# Power_Supply.net
KiCad netlist of a schematic drawn in EAGLE
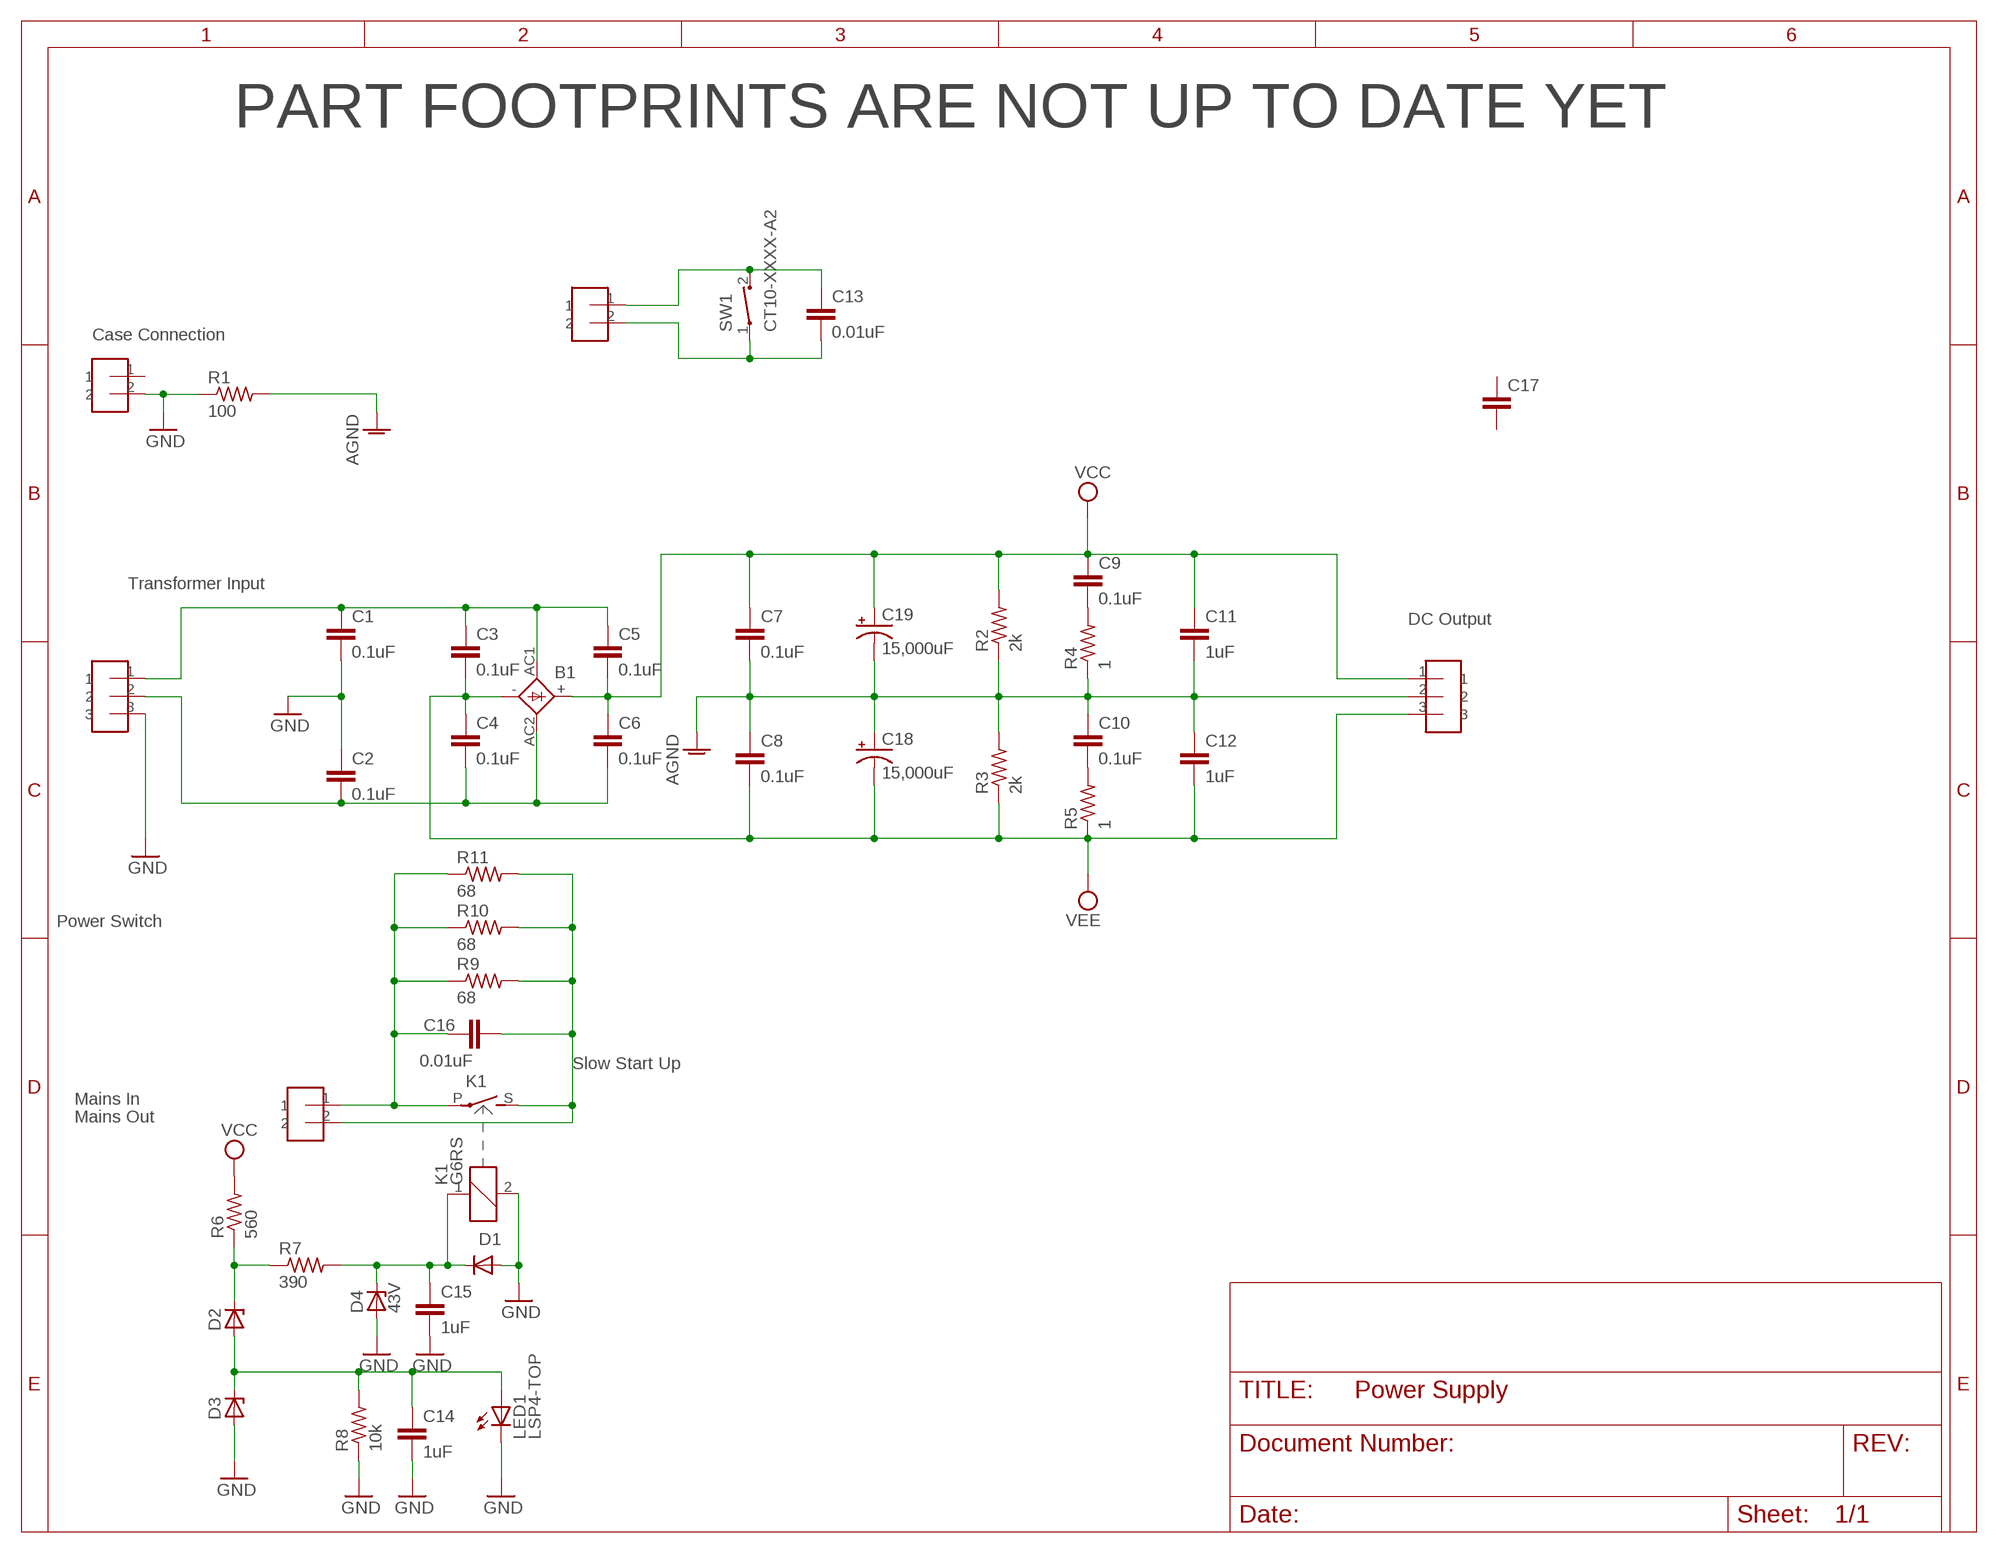
[diagram p0: schematic, sheet 1]

(export (version "E")
  (design (tool "Eeschema 10.0.6"))
  (components
    (comp (ref "B1")
      (value "GBPC1")
      (footprint "eagle-import:GBPC1")
      (libsource (lib "eagle-import") (part "GBPC1"))
    )
    (comp (ref "C1")
      (value "0.1uF")
      (footprint "eagle-import:C025-060X050")
      (libsource (lib "eagle-import") (part "C-EU025-060X050"))
    )
    (comp (ref "C2")
      (value "0.1uF")
      (footprint "eagle-import:C025-060X050")
      (libsource (lib "eagle-import") (part "C-EU025-060X050"))
    )
    (comp (ref "C3")
      (value "0.1uF")
      (footprint "eagle-import:C025-060X050")
      (libsource (lib "eagle-import") (part "C-EU025-060X050"))
    )
    (comp (ref "C4")
      (value "0.1uF")
      (footprint "eagle-import:C025-060X050")
      (libsource (lib "eagle-import") (part "C-EU025-060X050"))
    )
    (comp (ref "C5")
      (value "0.1uF")
      (footprint "eagle-import:C025-060X050")
      (libsource (lib "eagle-import") (part "C-EU025-060X050"))
    )
    (comp (ref "C6")
      (value "0.1uF")
      (footprint "eagle-import:C025-060X050")
      (libsource (lib "eagle-import") (part "C-EU025-060X050"))
    )
    (comp (ref "C7")
      (value "0.1uF")
      (footprint "eagle-import:C025-060X050")
      (libsource (lib "eagle-import") (part "C-EU025-060X050"))
    )
    (comp (ref "C8")
      (value "0.1uF")
      (footprint "eagle-import:C025-060X050")
      (libsource (lib "eagle-import") (part "C-EU025-060X050"))
    )
    (comp (ref "C9")
      (value "0.1uF")
      (footprint "eagle-import:C025-060X050")
      (libsource (lib "eagle-import") (part "C-EU025-060X050"))
    )
    (comp (ref "C10")
      (value "0.1uF")
      (footprint "eagle-import:C025-060X050")
      (libsource (lib "eagle-import") (part "C-EU025-060X050"))
    )
    (comp (ref "C11")
      (value "1uF")
      (footprint "eagle-import:C025-060X050")
      (libsource (lib "eagle-import") (part "C-EU025-060X050"))
    )
    (comp (ref "C12")
      (value "1uF")
      (footprint "eagle-import:C025-060X050")
      (libsource (lib "eagle-import") (part "C-EU025-060X050"))
    )
    (comp (ref "C13")
      (value "0.01uF")
      (footprint "eagle-import:C025-060X050")
      (libsource (lib "eagle-import") (part "C-EU025-060X050"))
    )
    (comp (ref "C14")
      (value "1uF")
      (footprint "eagle-import:C025-060X050")
      (libsource (lib "eagle-import") (part "C-EU025-060X050"))
    )
    (comp (ref "C15")
      (value "1uF")
      (footprint "eagle-import:C025-060X050")
      (libsource (lib "eagle-import") (part "C-EU025-060X050"))
    )
    (comp (ref "C16")
      (value "0.01uF")
      (footprint "eagle-import:C025-060X050")
      (libsource (lib "eagle-import") (part "C-EU025-060X050"))
    )
    (comp (ref "C17")
      (value "C-EU025-060X050")
      (footprint "eagle-import:C025-060X050")
      (libsource (lib "eagle-import") (part "C-EU025-060X050"))
    )
    (comp (ref "C18")
      (value "15,000uF")
      (footprint "eagle-import:E7,5-16")
      (libsource (lib "eagle-import") (part "CPOL-USE7.5-16"))
    )
    (comp (ref "C19")
      (value "15,000uF")
      (footprint "eagle-import:E7,5-16")
      (libsource (lib "eagle-import") (part "CPOL-USE7.5-16"))
    )
    (comp (ref "D1")
      (value "1N4004")
      (footprint "eagle-import:DO41-10")
      (libsource (lib "eagle-import") (part "1N4004"))
    )
    (comp (ref "D2")
      (value "ZENER-DIODEDO34-7")
      (footprint "eagle-import:DO34Z7")
      (libsource (lib "eagle-import") (part "ZENER-DIODEDO34-7"))
    )
    (comp (ref "D3")
      (value "ZENER-DIODEDO34-7")
      (footprint "eagle-import:DO34Z7")
      (libsource (lib "eagle-import") (part "ZENER-DIODEDO34-7"))
    )
    (comp (ref "D4")
      (value "43V")
      (footprint "eagle-import:DO34Z7")
      (libsource (lib "eagle-import") (part "ZENER-DIODEDO34-7"))
    )
    (comp (ref "K1")
      (value "G6RS")
      (footprint "eagle-import:G6RS")
      (libsource (lib "eagle-import") (part "G6RS"))
    )
    (comp (ref "LED1")
      (value "LSP4-TOP")
      (footprint "eagle-import:P47F-TOP")
      (libsource (lib "eagle-import") (part "P4-TOPLS"))
    )
    (comp (ref "R1")
      (value "100")
      (footprint "eagle-import:0617_22")
      (libsource (lib "eagle-import") (part "R-US_0617/22"))
    )
    (comp (ref "R2")
      (value "2k")
      (footprint "eagle-import:0617_22")
      (libsource (lib "eagle-import") (part "R-US_0617/22"))
    )
    (comp (ref "R3")
      (value "2k")
      (footprint "eagle-import:0617_22")
      (libsource (lib "eagle-import") (part "R-US_0617/22"))
    )
    (comp (ref "R4")
      (value "1")
      (footprint "eagle-import:0617_22")
      (libsource (lib "eagle-import") (part "R-US_0617/22"))
    )
    (comp (ref "R5")
      (value "1")
      (footprint "eagle-import:0617_22")
      (libsource (lib "eagle-import") (part "R-US_0617/22"))
    )
    (comp (ref "R6")
      (value "560")
      (footprint "eagle-import:0617_22")
      (libsource (lib "eagle-import") (part "R-US_0617/22"))
    )
    (comp (ref "R7")
      (value "390")
      (footprint "eagle-import:0617_22")
      (libsource (lib "eagle-import") (part "R-US_0617/22"))
    )
    (comp (ref "R8")
      (value "10k")
      (footprint "eagle-import:0617_22")
      (libsource (lib "eagle-import") (part "R-US_0617/22"))
    )
    (comp (ref "R9")
      (value "68")
      (footprint "eagle-import:0617_22")
      (libsource (lib "eagle-import") (part "R-US_0617/22"))
    )
    (comp (ref "R10")
      (value "68")
      (footprint "eagle-import:0617_22")
      (libsource (lib "eagle-import") (part "R-US_0617/22"))
    )
    (comp (ref "R11")
      (value "68")
      (footprint "eagle-import:0617_22")
      (libsource (lib "eagle-import") (part "R-US_0617/22"))
    )
    (comp (ref "SW1")
      (value "CT10-XXXX-A2")
      (footprint "eagle-import:CT10-XXXX-A2")
      (libsource (lib "eagle-import") (part "CT10-XXXX-A2"))
    )
    (comp (ref "U$1")
      (value "1X3HEADER_100MIL")
      (footprint "eagle-import:1X3_100MIL")
      (libsource (lib "eagle-import") (part "1X3HEADER_100MIL"))
    )
    (comp (ref "U$2")
      (value "1X3HEADER_100MIL")
      (footprint "eagle-import:1X3_100MIL")
      (libsource (lib "eagle-import") (part "1X3HEADER_100MIL"))
    )
    (comp (ref "U$3")
      (value "1X2HEADER_100MIL")
      (footprint "eagle-import:1X2_100MIL")
      (libsource (lib "eagle-import") (part "1X2HEADER_100MIL"))
    )
    (comp (ref "U$4")
      (value "1X2HEADER_100MIL")
      (footprint "eagle-import:1X2_100MIL")
      (libsource (lib "eagle-import") (part "1X2HEADER_100MIL"))
    )
    (comp (ref "U$5")
      (value "1X2HEADER_100MIL")
      (footprint "eagle-import:1X2_100MIL")
      (libsource (lib "eagle-import") (part "1X2HEADER_100MIL"))
    )
  )
  (nets
    (net (code "1") (name "AGND") (class "Default")
      (node (ref "C10") (pin "1") (pinfunction "1_1") (pintype "passive"))
      (node (ref "C11") (pin "2") (pinfunction "2_2") (pintype "passive"))
      (node (ref "C12") (pin "1") (pinfunction "1_1") (pintype "passive"))
      (node (ref "C18") (pin "+") (pinfunction "+_+") (pintype "passive"))
      (node (ref "C19") (pin "-") (pinfunction "-_-") (pintype "passive"))
      (node (ref "C7") (pin "2") (pinfunction "2_2") (pintype "passive"))
      (node (ref "C8") (pin "1") (pinfunction "1_1") (pintype "passive"))
      (node (ref "R1") (pin "2") (pinfunction "2_2") (pintype "passive"))
      (node (ref "R2") (pin "1") (pinfunction "1_1") (pintype "passive"))
      (node (ref "R3") (pin "2") (pinfunction "2_2") (pintype "passive"))
      (node (ref "R4") (pin "1") (pinfunction "1_1") (pintype "passive"))
      (node (ref "U$2") (pin "2") (pinfunction "2_2") (pintype "bidirectional"))
    )
    (net (code "2") (name "GND") (class "Default")
      (node (ref "C1") (pin "2") (pinfunction "2_2") (pintype "passive"))
      (node (ref "C14") (pin "2") (pinfunction "2_2") (pintype "passive"))
      (node (ref "C15") (pin "2") (pinfunction "2_2") (pintype "passive"))
      (node (ref "C2") (pin "1") (pinfunction "1_1") (pintype "passive"))
      (node (ref "D1") (pin "A") (pinfunction "A_A") (pintype "passive"))
      (node (ref "D3") (pin "A") (pinfunction "A_A") (pintype "passive"))
      (node (ref "D4") (pin "A") (pinfunction "A_A") (pintype "passive"))
      (node (ref "K1") (pin "2") (pinfunction "2_2") (pintype "passive"))
      (node (ref "LED1") (pin "C") (pinfunction "C_C") (pintype "passive"))
      (node (ref "R1") (pin "1") (pinfunction "1_1") (pintype "passive"))
      (node (ref "R8") (pin "1") (pinfunction "1_1") (pintype "passive"))
      (node (ref "U$1") (pin "3") (pinfunction "3_3") (pintype "bidirectional"))
      (node (ref "U$3") (pin "2") (pinfunction "2_2") (pintype "bidirectional"))
    )
    (net (code "3") (name "Net-(B1-PadAC1)") (class "Default")
      (node (ref "B1") (pin "AC1") (pinfunction "AC1_AC1") (pintype "passive"))
      (node (ref "C1") (pin "1") (pinfunction "1_1") (pintype "passive"))
      (node (ref "C3") (pin "1") (pinfunction "1_1") (pintype "passive"))
      (node (ref "C5") (pin "1") (pinfunction "1_1") (pintype "passive"))
      (node (ref "U$1") (pin "1") (pinfunction "1_1") (pintype "bidirectional"))
    )
    (net (code "4") (name "Net-(B1-PadAC2)") (class "Default")
      (node (ref "B1") (pin "AC2") (pinfunction "AC2_AC2") (pintype "passive"))
      (node (ref "C2") (pin "2") (pinfunction "2_2") (pintype "passive"))
      (node (ref "C4") (pin "2") (pinfunction "2_2") (pintype "passive"))
      (node (ref "C6") (pin "2") (pinfunction "2_2") (pintype "passive"))
      (node (ref "U$1") (pin "2") (pinfunction "2_2") (pintype "bidirectional"))
    )
    (net (code "5") (name "Net-(C9-Pad2)") (class "Default")
      (node (ref "C9") (pin "2") (pinfunction "2_2") (pintype "passive"))
      (node (ref "R4") (pin "2") (pinfunction "2_2") (pintype "passive"))
    )
    (net (code "6") (name "Net-(C10-Pad2)") (class "Default")
      (node (ref "C10") (pin "2") (pinfunction "2_2") (pintype "passive"))
      (node (ref "R5") (pin "2") (pinfunction "2_2") (pintype "passive"))
    )
    (net (code "7") (name "Net-(C13-Pad1)") (class "Default")
      (node (ref "C13") (pin "1") (pinfunction "1_1") (pintype "passive"))
      (node (ref "SW1") (pin "2") (pinfunction "2_2") (pintype "passive"))
      (node (ref "U$5") (pin "1") (pinfunction "1_1") (pintype "bidirectional"))
    )
    (net (code "8") (name "Net-(C13-Pad2)") (class "Default")
      (node (ref "C13") (pin "2") (pinfunction "2_2") (pintype "passive"))
      (node (ref "SW1") (pin "1") (pinfunction "1_1") (pintype "passive"))
      (node (ref "U$5") (pin "2") (pinfunction "2_2") (pintype "bidirectional"))
    )
    (net (code "9") (name "Net-(C14-Pad1)") (class "Default")
      (node (ref "C14") (pin "1") (pinfunction "1_1") (pintype "passive"))
      (node (ref "D2") (pin "A") (pinfunction "A_A") (pintype "passive"))
      (node (ref "D3") (pin "C") (pinfunction "C_C") (pintype "passive"))
      (node (ref "LED1") (pin "A") (pinfunction "A_A") (pintype "passive"))
      (node (ref "R8") (pin "2") (pinfunction "2_2") (pintype "passive"))
    )
    (net (code "10") (name "Net-(C15-Pad1)") (class "Default")
      (node (ref "C15") (pin "1") (pinfunction "1_1") (pintype "passive"))
      (node (ref "D1") (pin "C") (pinfunction "C_C") (pintype "passive"))
      (node (ref "D4") (pin "C") (pinfunction "C_C") (pintype "passive"))
      (node (ref "K1") (pin "1") (pinfunction "1_1") (pintype "passive"))
      (node (ref "R7") (pin "2") (pinfunction "2_2") (pintype "passive"))
    )
    (net (code "11") (name "Net-(C16-Pad1)") (class "Default")
      (node (ref "C16") (pin "1") (pinfunction "1_1") (pintype "passive"))
      (node (ref "K1") (pin "P") (pinfunction "P_P") (pintype "passive"))
      (node (ref "R10") (pin "1") (pinfunction "1_1") (pintype "passive"))
      (node (ref "R11") (pin "1") (pinfunction "1_1") (pintype "passive"))
      (node (ref "R9") (pin "1") (pinfunction "1_1") (pintype "passive"))
      (node (ref "U$4") (pin "1") (pinfunction "1_1") (pintype "bidirectional"))
    )
    (net (code "12") (name "Net-(C16-Pad2)") (class "Default")
      (node (ref "C16") (pin "2") (pinfunction "2_2") (pintype "passive"))
      (node (ref "K1") (pin "S") (pinfunction "S_S") (pintype "passive"))
      (node (ref "R10") (pin "2") (pinfunction "2_2") (pintype "passive"))
      (node (ref "R11") (pin "2") (pinfunction "2_2") (pintype "passive"))
      (node (ref "R9") (pin "2") (pinfunction "2_2") (pintype "passive"))
      (node (ref "U$4") (pin "2") (pinfunction "2_2") (pintype "bidirectional"))
    )
    (net (code "13") (name "Net-(D2-PadC)") (class "Default")
      (node (ref "D2") (pin "C") (pinfunction "C_C") (pintype "passive"))
      (node (ref "R6") (pin "1") (pinfunction "1_1") (pintype "passive"))
      (node (ref "R7") (pin "1") (pinfunction "1_1") (pintype "passive"))
    )
    (net (code "14") (name "VCC") (class "Default")
      (node (ref "B1") (pin "+") (pinfunction "+_+") (pintype "passive"))
      (node (ref "C11") (pin "1") (pinfunction "1_1") (pintype "passive"))
      (node (ref "C19") (pin "+") (pinfunction "+_+") (pintype "passive"))
      (node (ref "C5") (pin "2") (pinfunction "2_2") (pintype "passive"))
      (node (ref "C6") (pin "1") (pinfunction "1_1") (pintype "passive"))
      (node (ref "C7") (pin "1") (pinfunction "1_1") (pintype "passive"))
      (node (ref "C9") (pin "1") (pinfunction "1_1") (pintype "passive"))
      (node (ref "R2") (pin "2") (pinfunction "2_2") (pintype "passive"))
      (node (ref "R6") (pin "2") (pinfunction "2_2") (pintype "passive"))
      (node (ref "U$2") (pin "1") (pinfunction "1_1") (pintype "bidirectional"))
    )
    (net (code "15") (name "VEE") (class "Default")
      (node (ref "B1") (pin "-") (pinfunction "-_-") (pintype "passive"))
      (node (ref "C12") (pin "2") (pinfunction "2_2") (pintype "passive"))
      (node (ref "C18") (pin "-") (pinfunction "-_-") (pintype "passive"))
      (node (ref "C3") (pin "2") (pinfunction "2_2") (pintype "passive"))
      (node (ref "C4") (pin "1") (pinfunction "1_1") (pintype "passive"))
      (node (ref "C8") (pin "2") (pinfunction "2_2") (pintype "passive"))
      (node (ref "R3") (pin "1") (pinfunction "1_1") (pintype "passive"))
      (node (ref "R5") (pin "1") (pinfunction "1_1") (pintype "passive"))
      (node (ref "U$2") (pin "3") (pinfunction "3_3") (pintype "bidirectional"))
    )
    (net (code "16") (name "unconnected-(C17-Pad1)") (class "Default")
      (node (ref "C17") (pin "1") (pinfunction "1_1") (pintype "passive"))
    )
    (net (code "17") (name "unconnected-(C17-Pad2)") (class "Default")
      (node (ref "C17") (pin "2") (pinfunction "2_2") (pintype "passive"))
    )
    (net (code "18") (name "unconnected-(U$3-Pad1)") (class "Default")
      (node (ref "U$3") (pin "1") (pinfunction "1_1") (pintype "bidirectional"))
    )
  )
)
